# encoder_breakout.net
KiCad netlist of a schematic drawn in EAGLE
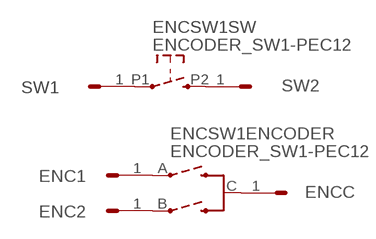
[diagram p0: schematic, sheet 1]

(export (version "E")
  (design (tool "Eeschema 10.0.6"))
  (components
    (comp (ref "ENC1")
      (value "HEADER/MALE/01")
      (footprint "eagle-import:HEADER_MALE_01")
      (libsource (lib "eagle-import") (part "HEADER/MALE/01"))
    )
    (comp (ref "ENC2")
      (value "HEADER/MALE/01")
      (footprint "eagle-import:HEADER_MALE_01")
      (libsource (lib "eagle-import") (part "HEADER/MALE/01"))
    )
    (comp (ref "ENCC")
      (value "HEADER/MALE/01")
      (footprint "eagle-import:HEADER_MALE_01")
      (libsource (lib "eagle-import") (part "HEADER/MALE/01"))
    )
    (comp (ref "ENCSW1")
      (value "ENCODER_SW1-PEC12")
      (footprint "eagle-import:PEC12_INCREMENTAL_ENCODER")
      (libsource (lib "eagle-import") (part "ENCODER_SW1-PEC12"))
    )
    (comp (ref "SW1")
      (value "HEADER/MALE/01")
      (footprint "eagle-import:HEADER_MALE_01")
      (libsource (lib "eagle-import") (part "HEADER/MALE/01"))
    )
    (comp (ref "SW2")
      (value "HEADER/MALE/01")
      (footprint "eagle-import:HEADER_MALE_01")
      (libsource (lib "eagle-import") (part "HEADER/MALE/01"))
    )
  )
  (nets
    (net (code "1") (name "Net-(ENC1-3)") (class "Default")
      (node (ref "ENC1") (pin "1") (pinfunction "3_1") (pintype "passive"))
      (node (ref "ENCSW1") (pin "A") (pinfunction "A_A") (pintype "passive"))
    )
    (net (code "2") (name "Net-(ENC2-3)") (class "Default")
      (node (ref "ENC2") (pin "1") (pinfunction "3_1") (pintype "passive"))
      (node (ref "ENCSW1") (pin "B") (pinfunction "B_B") (pintype "passive"))
    )
    (net (code "3") (name "Net-(ENCC-3)") (class "Default")
      (node (ref "ENCC") (pin "1") (pinfunction "3_1") (pintype "passive"))
      (node (ref "ENCSW1") (pin "C") (pinfunction "C_C") (pintype "passive"))
    )
    (net (code "4") (name "Net-(ENCSW1B-1)") (class "Default")
      (node (ref "ENCSW1") (pin "P1") (pinfunction "1_P1") (pintype "passive"))
      (node (ref "SW1") (pin "1") (pinfunction "3_1") (pintype "passive"))
    )
    (net (code "5") (name "Net-(ENCSW1B-2)") (class "Default")
      (node (ref "ENCSW1") (pin "P2") (pinfunction "2_P2") (pintype "passive"))
      (node (ref "SW2") (pin "1") (pinfunction "3_1") (pintype "passive"))
    )
  )
)
